# SDDD-PulseBoard-1_0.net
KiCad netlist of a schematic drawn in EAGLE
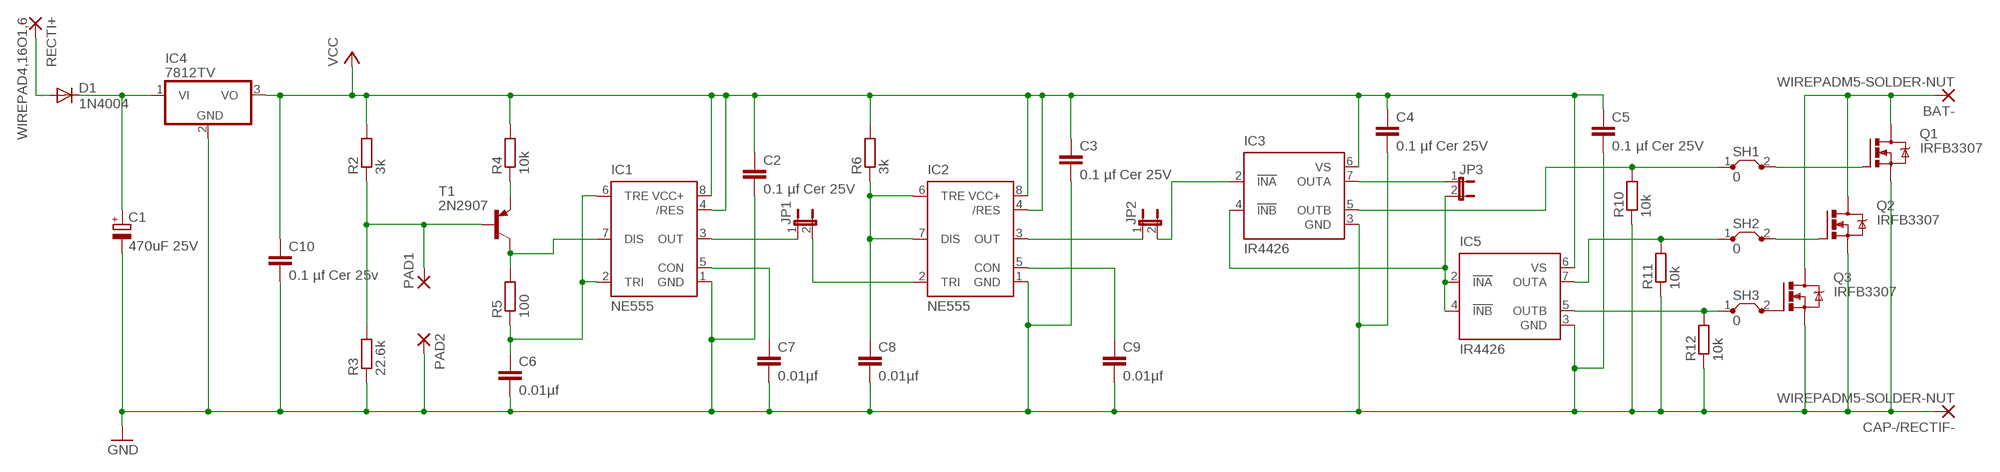
[diagram p0: schematic, sheet 1]

(export (version "E")
  (design (tool "Eeschema 10.0.6"))
  (components
    (comp (ref "BAT-")
      (value "WIREPADM5-SOLDER-NUT")
      (footprint "eagle-import:M5-SOLDER-NUT")
      (libsource (lib "eagle-import") (part "WIREPADM5-SOLDER-NUT"))
    )
    (comp (ref "C1")
      (value "470uF 25V")
      (footprint "eagle-import:E5-8,5")
      (libsource (lib "eagle-import") (part "CPOL-EUE5-8.5"))
    )
    (comp (ref "C2")
      (value "0.1 µf Cer 25V")
      (footprint "eagle-import:C050-025X075")
      (libsource (lib "eagle-import") (part "C-EU050-025X075"))
    )
    (comp (ref "C3")
      (value "0.1 µf Cer 25V")
      (footprint "eagle-import:C050-025X075")
      (libsource (lib "eagle-import") (part "C-EU050-025X075"))
    )
    (comp (ref "C4")
      (value "0.1 µf Cer 25V")
      (footprint "eagle-import:C050-025X075")
      (libsource (lib "eagle-import") (part "C-EU050-025X075"))
    )
    (comp (ref "C5")
      (value "0.1 µf Cer 25V")
      (footprint "eagle-import:C050-025X075")
      (libsource (lib "eagle-import") (part "C-EU050-025X075"))
    )
    (comp (ref "C6")
      (value "0.01µf")
      (footprint "eagle-import:C050-025X075")
      (libsource (lib "eagle-import") (part "C-EU050-025X075"))
    )
    (comp (ref "C7")
      (value "0.01µf")
      (footprint "eagle-import:C050-025X075")
      (libsource (lib "eagle-import") (part "C-EU050-025X075"))
    )
    (comp (ref "C8")
      (value "0.01µf")
      (footprint "eagle-import:C050-025X075")
      (libsource (lib "eagle-import") (part "C-EU050-025X075"))
    )
    (comp (ref "C9")
      (value "0.01µf")
      (footprint "eagle-import:C050-025X075")
      (libsource (lib "eagle-import") (part "C-EU050-025X075"))
    )
    (comp (ref "C10")
      (value "0.1 µf Cer 25v")
      (footprint "eagle-import:C050-025X075")
      (libsource (lib "eagle-import") (part "C-EU050-025X075"))
    )
    (comp (ref "CAP-/RECTIF-")
      (value "WIREPADM5-SOLDER-NUT")
      (footprint "eagle-import:M5-SOLDER-NUT")
      (libsource (lib "eagle-import") (part "WIREPADM5-SOLDER-NUT"))
    )
    (comp (ref "D1")
      (value "1N4004")
      (footprint "eagle-import:DO41-10")
      (libsource (lib "eagle-import") (part "1N4004"))
    )
    (comp (ref "IC1")
      (value "NE555")
      (footprint "eagle-import:DIL-08")
      (fields (field (name "MF") "Arrow Electronics") (field (name "MPN") "NE555N"))
      (libsource (lib "eagle-import") (part "NE555"))
    )
    (comp (ref "IC2")
      (value "NE555")
      (footprint "eagle-import:DIL-08")
      (fields (field (name "MF") "Arrow Electronics") (field (name "MPN") "NE555N"))
      (libsource (lib "eagle-import") (part "NE555"))
    )
    (comp (ref "IC3")
      (value "IR4426")
      (footprint "eagle-import:DIL08")
      (fields (field (name "MF") "INTERNATIONAL RECTIFIER(IR)") (field (name "MPN") "IR4426PBF"))
      (libsource (lib "eagle-import") (part "IR4426"))
    )
    (comp (ref "IC4")
      (value "7812TV")
      (footprint "eagle-import:TO220V")
      (libsource (lib "eagle-import") (part "78TV12"))
    )
    (comp (ref "IC5")
      (value "IR4426")
      (footprint "eagle-import:DIL08")
      (fields (field (name "MF") "INTERNATIONAL RECTIFIER(IR)") (field (name "MPN") "IR4426PBF"))
      (libsource (lib "eagle-import") (part "IR4426"))
    )
    (comp (ref "JP1")
      (value "JP1E")
      (footprint "eagle-import:JP1")
      (libsource (lib "eagle-import") (part "JP1E"))
    )
    (comp (ref "JP2")
      (value "JP1E")
      (footprint "eagle-import:JP1")
      (libsource (lib "eagle-import") (part "JP1E"))
    )
    (comp (ref "JP3")
      (value "JP1E")
      (footprint "eagle-import:JP1")
      (libsource (lib "eagle-import") (part "JP1E"))
    )
    (comp (ref "PAD1")
      (value "2,15/1,0")
      (footprint "eagle-import:2,15_1,0")
      (libsource (lib "eagle-import") (part "2,15/1,0"))
    )
    (comp (ref "PAD2")
      (value "2,15/1,0")
      (footprint "eagle-import:2,15_1,0")
      (libsource (lib "eagle-import") (part "2,15/1,0"))
    )
    (comp (ref "Q1")
      (value "IRFB3307")
      (footprint "eagle-import:TO220BV")
      (libsource (lib "eagle-import") (part "IRF540"))
    )
    (comp (ref "Q2")
      (value "IRFB3307")
      (footprint "eagle-import:TO220BV")
      (libsource (lib "eagle-import") (part "IRF540"))
    )
    (comp (ref "Q3")
      (value "IRFB3307")
      (footprint "eagle-import:TO220BV")
      (libsource (lib "eagle-import") (part "IRF540"))
    )
    (comp (ref "R2")
      (value "3k")
      (footprint "eagle-import:0207_10")
      (libsource (lib "eagle-import") (part "R-EU_0207/10"))
    )
    (comp (ref "R3")
      (value "22.6k")
      (footprint "eagle-import:0207_10")
      (libsource (lib "eagle-import") (part "R-EU_0207/10"))
    )
    (comp (ref "R4")
      (value "10k")
      (footprint "eagle-import:0207_10")
      (libsource (lib "eagle-import") (part "R-EU_0207/10"))
    )
    (comp (ref "R5")
      (value "100")
      (footprint "eagle-import:0207_10")
      (libsource (lib "eagle-import") (part "R-EU_0207/10"))
    )
    (comp (ref "R6")
      (value "3k")
      (footprint "eagle-import:0207_10")
      (libsource (lib "eagle-import") (part "R-EU_0207/10"))
    )
    (comp (ref "R10")
      (value "10k")
      (footprint "eagle-import:0207_10")
      (libsource (lib "eagle-import") (part "R-EU_0207/10"))
    )
    (comp (ref "R11")
      (value "10k")
      (footprint "eagle-import:0207_10")
      (libsource (lib "eagle-import") (part "R-EU_0207/10"))
    )
    (comp (ref "R12")
      (value "10k")
      (footprint "eagle-import:0207_10")
      (libsource (lib "eagle-import") (part "R-EU_0207/10"))
    )
    (comp (ref "RECTI+")
      (value "WIREPAD4,16O1,6")
      (footprint "eagle-import:4,16O1,6")
      (libsource (lib "eagle-import") (part "WIREPAD4,16O1,6"))
    )
    (comp (ref "SH1")
      (value "0")
      (footprint "eagle-import:30")
      (libsource (lib "eagle-import") (part "J30MM"))
    )
    (comp (ref "SH2")
      (value "0")
      (footprint "eagle-import:30")
      (libsource (lib "eagle-import") (part "J30MM"))
    )
    (comp (ref "SH3")
      (value "0")
      (footprint "eagle-import:30")
      (libsource (lib "eagle-import") (part "J30MM"))
    )
    (comp (ref "T1")
      (value "2N2907")
      (footprint "eagle-import:TO92-CBE")
      (libsource (lib "eagle-import") (part "-PNP-TO92-CBEMPS2907A"))
    )
  )
  (nets
    (net (code "1") (name "GND") (class "Default")
      (node (ref "C1") (pin "-") (pinfunction "-_-") (pintype "passive"))
      (node (ref "C10") (pin "2") (pinfunction "2_2") (pintype "passive"))
      (node (ref "C2") (pin "2") (pinfunction "2_2") (pintype "passive"))
      (node (ref "C3") (pin "2") (pinfunction "2_2") (pintype "passive"))
      (node (ref "C4") (pin "2") (pinfunction "2_2") (pintype "passive"))
      (node (ref "C5") (pin "2") (pinfunction "2_2") (pintype "passive"))
      (node (ref "C6") (pin "2") (pinfunction "2_2") (pintype "passive"))
      (node (ref "C7") (pin "2") (pinfunction "2_2") (pintype "passive"))
      (node (ref "C8") (pin "2") (pinfunction "2_2") (pintype "passive"))
      (node (ref "C9") (pin "2") (pinfunction "2_2") (pintype "passive"))
      (node (ref "CAP-/RECTIF-") (pin "1") (pinfunction "P_1") (pintype "passive"))
      (node (ref "CAP-/RECTIF-") (pin "P$1") (pinfunction "P_P$1") (pintype "passive"))
      (node (ref "CAP-/RECTIF-") (pin "P$10") (pinfunction "P_P$10") (pintype "passive"))
      (node (ref "CAP-/RECTIF-") (pin "P$11") (pinfunction "P_P$11") (pintype "passive"))
      (node (ref "CAP-/RECTIF-") (pin "P$12") (pinfunction "P_P$12") (pintype "passive"))
      (node (ref "CAP-/RECTIF-") (pin "P$13") (pinfunction "P_P$13") (pintype "passive"))
      (node (ref "CAP-/RECTIF-") (pin "P$14") (pinfunction "P_P$14") (pintype "passive"))
      (node (ref "CAP-/RECTIF-") (pin "P$15") (pinfunction "P_P$15") (pintype "passive"))
      (node (ref "CAP-/RECTIF-") (pin "P$16") (pinfunction "P_P$16") (pintype "passive"))
      (node (ref "CAP-/RECTIF-") (pin "P$17") (pinfunction "P_P$17") (pintype "passive"))
      (node (ref "CAP-/RECTIF-") (pin "P$18") (pinfunction "P_P$18") (pintype "passive"))
      (node (ref "CAP-/RECTIF-") (pin "P$19") (pinfunction "P_P$19") (pintype "passive"))
      (node (ref "CAP-/RECTIF-") (pin "P$2") (pinfunction "P_P$2") (pintype "passive"))
      (node (ref "CAP-/RECTIF-") (pin "P$20") (pinfunction "P_P$20") (pintype "passive"))
      (node (ref "CAP-/RECTIF-") (pin "P$21") (pinfunction "P_P$21") (pintype "passive"))
      (node (ref "CAP-/RECTIF-") (pin "P$22") (pinfunction "P_P$22") (pintype "passive"))
      (node (ref "CAP-/RECTIF-") (pin "P$23") (pinfunction "P_P$23") (pintype "passive"))
      (node (ref "CAP-/RECTIF-") (pin "P$24") (pinfunction "P_P$24") (pintype "passive"))
      (node (ref "CAP-/RECTIF-") (pin "P$25") (pinfunction "P_P$25") (pintype "passive"))
      (node (ref "CAP-/RECTIF-") (pin "P$26") (pinfunction "P_P$26") (pintype "passive"))
      (node (ref "CAP-/RECTIF-") (pin "P$27") (pinfunction "P_P$27") (pintype "passive"))
      (node (ref "CAP-/RECTIF-") (pin "P$28") (pinfunction "P_P$28") (pintype "passive"))
      (node (ref "CAP-/RECTIF-") (pin "P$29") (pinfunction "P_P$29") (pintype "passive"))
      (node (ref "CAP-/RECTIF-") (pin "P$3") (pinfunction "P_P$3") (pintype "passive"))
      (node (ref "CAP-/RECTIF-") (pin "P$30") (pinfunction "P_P$30") (pintype "passive"))
      (node (ref "CAP-/RECTIF-") (pin "P$31") (pinfunction "P_P$31") (pintype "passive"))
      (node (ref "CAP-/RECTIF-") (pin "P$32") (pinfunction "P_P$32") (pintype "passive"))
      (node (ref "CAP-/RECTIF-") (pin "P$33") (pinfunction "P_P$33") (pintype "passive"))
      (node (ref "CAP-/RECTIF-") (pin "P$34") (pinfunction "P_P$34") (pintype "passive"))
      (node (ref "CAP-/RECTIF-") (pin "P$35") (pinfunction "P_P$35") (pintype "passive"))
      (node (ref "CAP-/RECTIF-") (pin "P$36") (pinfunction "P_P$36") (pintype "passive"))
      (node (ref "CAP-/RECTIF-") (pin "P$37") (pinfunction "P_P$37") (pintype "passive"))
      (node (ref "CAP-/RECTIF-") (pin "P$38") (pinfunction "P_P$38") (pintype "passive"))
      (node (ref "CAP-/RECTIF-") (pin "P$39") (pinfunction "P_P$39") (pintype "passive"))
      (node (ref "CAP-/RECTIF-") (pin "P$4") (pinfunction "P_P$4") (pintype "passive"))
      (node (ref "CAP-/RECTIF-") (pin "P$40") (pinfunction "P_P$40") (pintype "passive"))
      (node (ref "CAP-/RECTIF-") (pin "P$41") (pinfunction "P_P$41") (pintype "passive"))
      (node (ref "CAP-/RECTIF-") (pin "P$42") (pinfunction "P_P$42") (pintype "passive"))
      (node (ref "CAP-/RECTIF-") (pin "P$43") (pinfunction "P_P$43") (pintype "passive"))
      (node (ref "CAP-/RECTIF-") (pin "P$44") (pinfunction "P_P$44") (pintype "passive"))
      (node (ref "CAP-/RECTIF-") (pin "P$45") (pinfunction "P_P$45") (pintype "passive"))
      (node (ref "CAP-/RECTIF-") (pin "P$46") (pinfunction "P_P$46") (pintype "passive"))
      (node (ref "CAP-/RECTIF-") (pin "P$47") (pinfunction "P_P$47") (pintype "passive"))
      (node (ref "CAP-/RECTIF-") (pin "P$48") (pinfunction "P_P$48") (pintype "passive"))
      (node (ref "CAP-/RECTIF-") (pin "P$49") (pinfunction "P_P$49") (pintype "passive"))
      (node (ref "CAP-/RECTIF-") (pin "P$5") (pinfunction "P_P$5") (pintype "passive"))
      (node (ref "CAP-/RECTIF-") (pin "P$50") (pinfunction "P_P$50") (pintype "passive"))
      (node (ref "CAP-/RECTIF-") (pin "P$51") (pinfunction "P_P$51") (pintype "passive"))
      (node (ref "CAP-/RECTIF-") (pin "P$52") (pinfunction "P_P$52") (pintype "passive"))
      (node (ref "CAP-/RECTIF-") (pin "P$53") (pinfunction "P_P$53") (pintype "passive"))
      (node (ref "CAP-/RECTIF-") (pin "P$54") (pinfunction "P_P$54") (pintype "passive"))
      (node (ref "CAP-/RECTIF-") (pin "P$55") (pinfunction "P_P$55") (pintype "passive"))
      (node (ref "CAP-/RECTIF-") (pin "P$56") (pinfunction "P_P$56") (pintype "passive"))
      (node (ref "CAP-/RECTIF-") (pin "P$57") (pinfunction "P_P$57") (pintype "passive"))
      (node (ref "CAP-/RECTIF-") (pin "P$58") (pinfunction "P_P$58") (pintype "passive"))
      (node (ref "CAP-/RECTIF-") (pin "P$59") (pinfunction "P_P$59") (pintype "passive"))
      (node (ref "CAP-/RECTIF-") (pin "P$6") (pinfunction "P_P$6") (pintype "passive"))
      (node (ref "CAP-/RECTIF-") (pin "P$60") (pinfunction "P_P$60") (pintype "passive"))
      (node (ref "CAP-/RECTIF-") (pin "P$61") (pinfunction "P_P$61") (pintype "passive"))
      (node (ref "CAP-/RECTIF-") (pin "P$62") (pinfunction "P_P$62") (pintype "passive"))
      (node (ref "CAP-/RECTIF-") (pin "P$63") (pinfunction "P_P$63") (pintype "passive"))
      (node (ref "CAP-/RECTIF-") (pin "P$64") (pinfunction "P_P$64") (pintype "passive"))
      (node (ref "CAP-/RECTIF-") (pin "P$65") (pinfunction "P_P$65") (pintype "passive"))
      (node (ref "CAP-/RECTIF-") (pin "P$66") (pinfunction "P_P$66") (pintype "passive"))
      (node (ref "CAP-/RECTIF-") (pin "P$67") (pinfunction "P_P$67") (pintype "passive"))
      (node (ref "CAP-/RECTIF-") (pin "P$68") (pinfunction "P_P$68") (pintype "passive"))
      (node (ref "CAP-/RECTIF-") (pin "P$69") (pinfunction "P_P$69") (pintype "passive"))
      (node (ref "CAP-/RECTIF-") (pin "P$7") (pinfunction "P_P$7") (pintype "passive"))
      (node (ref "CAP-/RECTIF-") (pin "P$70") (pinfunction "P_P$70") (pintype "passive"))
      (node (ref "CAP-/RECTIF-") (pin "P$71") (pinfunction "P_P$71") (pintype "passive"))
      (node (ref "CAP-/RECTIF-") (pin "P$72") (pinfunction "P_P$72") (pintype "passive"))
      (node (ref "CAP-/RECTIF-") (pin "P$73") (pinfunction "P_P$73") (pintype "passive"))
      (node (ref "CAP-/RECTIF-") (pin "P$74") (pinfunction "P_P$74") (pintype "passive"))
      (node (ref "CAP-/RECTIF-") (pin "P$75") (pinfunction "P_P$75") (pintype "passive"))
      (node (ref "CAP-/RECTIF-") (pin "P$76") (pinfunction "P_P$76") (pintype "passive"))
      (node (ref "CAP-/RECTIF-") (pin "P$77") (pinfunction "P_P$77") (pintype "passive"))
      (node (ref "CAP-/RECTIF-") (pin "P$78") (pinfunction "P_P$78") (pintype "passive"))
      (node (ref "CAP-/RECTIF-") (pin "P$79") (pinfunction "P_P$79") (pintype "passive"))
      (node (ref "CAP-/RECTIF-") (pin "P$8") (pinfunction "P_P$8") (pintype "passive"))
      (node (ref "CAP-/RECTIF-") (pin "P$80") (pinfunction "P_P$80") (pintype "passive"))
      (node (ref "CAP-/RECTIF-") (pin "P$9") (pinfunction "P_P$9") (pintype "passive"))
      (node (ref "IC1") (pin "1") (pinfunction "GND_1") (pintype "power_in"))
      (node (ref "IC2") (pin "1") (pinfunction "GND_1") (pintype "power_in"))
      (node (ref "IC3") (pin "3") (pinfunction "GND_3") (pintype "power_in"))
      (node (ref "IC4") (pin "2") (pinfunction "GND_2") (pintype "passive"))
      (node (ref "IC5") (pin "3") (pinfunction "GND_3") (pintype "power_in"))
      (node (ref "PAD2") (pin "1") (pinfunction "P_1") (pintype "passive"))
      (node (ref "Q1") (pin "S") (pinfunction "S_S") (pintype "passive"))
      (node (ref "Q2") (pin "S") (pinfunction "S_S") (pintype "passive"))
      (node (ref "Q3") (pin "S") (pinfunction "S_S") (pintype "passive"))
      (node (ref "R10") (pin "1") (pinfunction "1_1") (pintype "passive"))
      (node (ref "R11") (pin "1") (pinfunction "1_1") (pintype "passive"))
      (node (ref "R12") (pin "1") (pinfunction "1_1") (pintype "passive"))
      (node (ref "R3") (pin "1") (pinfunction "1_1") (pintype "passive"))
    )
    (net (code "2") (name "Net-(BAT--P-Pad1)") (class "Default")
      (node (ref "BAT-") (pin "1") (pinfunction "P_1") (pintype "passive"))
      (node (ref "BAT-") (pin "P$1") (pinfunction "P_P$1") (pintype "passive"))
      (node (ref "BAT-") (pin "P$10") (pinfunction "P_P$10") (pintype "passive"))
      (node (ref "BAT-") (pin "P$11") (pinfunction "P_P$11") (pintype "passive"))
      (node (ref "BAT-") (pin "P$12") (pinfunction "P_P$12") (pintype "passive"))
      (node (ref "BAT-") (pin "P$13") (pinfunction "P_P$13") (pintype "passive"))
      (node (ref "BAT-") (pin "P$14") (pinfunction "P_P$14") (pintype "passive"))
      (node (ref "BAT-") (pin "P$15") (pinfunction "P_P$15") (pintype "passive"))
      (node (ref "BAT-") (pin "P$16") (pinfunction "P_P$16") (pintype "passive"))
      (node (ref "BAT-") (pin "P$17") (pinfunction "P_P$17") (pintype "passive"))
      (node (ref "BAT-") (pin "P$18") (pinfunction "P_P$18") (pintype "passive"))
      (node (ref "BAT-") (pin "P$19") (pinfunction "P_P$19") (pintype "passive"))
      (node (ref "BAT-") (pin "P$2") (pinfunction "P_P$2") (pintype "passive"))
      (node (ref "BAT-") (pin "P$20") (pinfunction "P_P$20") (pintype "passive"))
      (node (ref "BAT-") (pin "P$21") (pinfunction "P_P$21") (pintype "passive"))
      (node (ref "BAT-") (pin "P$22") (pinfunction "P_P$22") (pintype "passive"))
      (node (ref "BAT-") (pin "P$23") (pinfunction "P_P$23") (pintype "passive"))
      (node (ref "BAT-") (pin "P$24") (pinfunction "P_P$24") (pintype "passive"))
      (node (ref "BAT-") (pin "P$25") (pinfunction "P_P$25") (pintype "passive"))
      (node (ref "BAT-") (pin "P$26") (pinfunction "P_P$26") (pintype "passive"))
      (node (ref "BAT-") (pin "P$27") (pinfunction "P_P$27") (pintype "passive"))
      (node (ref "BAT-") (pin "P$28") (pinfunction "P_P$28") (pintype "passive"))
      (node (ref "BAT-") (pin "P$29") (pinfunction "P_P$29") (pintype "passive"))
      (node (ref "BAT-") (pin "P$3") (pinfunction "P_P$3") (pintype "passive"))
      (node (ref "BAT-") (pin "P$30") (pinfunction "P_P$30") (pintype "passive"))
      (node (ref "BAT-") (pin "P$31") (pinfunction "P_P$31") (pintype "passive"))
      (node (ref "BAT-") (pin "P$32") (pinfunction "P_P$32") (pintype "passive"))
      (node (ref "BAT-") (pin "P$33") (pinfunction "P_P$33") (pintype "passive"))
      (node (ref "BAT-") (pin "P$34") (pinfunction "P_P$34") (pintype "passive"))
      (node (ref "BAT-") (pin "P$35") (pinfunction "P_P$35") (pintype "passive"))
      (node (ref "BAT-") (pin "P$36") (pinfunction "P_P$36") (pintype "passive"))
      (node (ref "BAT-") (pin "P$37") (pinfunction "P_P$37") (pintype "passive"))
      (node (ref "BAT-") (pin "P$38") (pinfunction "P_P$38") (pintype "passive"))
      (node (ref "BAT-") (pin "P$39") (pinfunction "P_P$39") (pintype "passive"))
      (node (ref "BAT-") (pin "P$4") (pinfunction "P_P$4") (pintype "passive"))
      (node (ref "BAT-") (pin "P$40") (pinfunction "P_P$40") (pintype "passive"))
      (node (ref "BAT-") (pin "P$41") (pinfunction "P_P$41") (pintype "passive"))
      (node (ref "BAT-") (pin "P$42") (pinfunction "P_P$42") (pintype "passive"))
      (node (ref "BAT-") (pin "P$43") (pinfunction "P_P$43") (pintype "passive"))
      (node (ref "BAT-") (pin "P$44") (pinfunction "P_P$44") (pintype "passive"))
      (node (ref "BAT-") (pin "P$45") (pinfunction "P_P$45") (pintype "passive"))
      (node (ref "BAT-") (pin "P$46") (pinfunction "P_P$46") (pintype "passive"))
      (node (ref "BAT-") (pin "P$47") (pinfunction "P_P$47") (pintype "passive"))
      (node (ref "BAT-") (pin "P$48") (pinfunction "P_P$48") (pintype "passive"))
      (node (ref "BAT-") (pin "P$49") (pinfunction "P_P$49") (pintype "passive"))
      (node (ref "BAT-") (pin "P$5") (pinfunction "P_P$5") (pintype "passive"))
      (node (ref "BAT-") (pin "P$50") (pinfunction "P_P$50") (pintype "passive"))
      (node (ref "BAT-") (pin "P$51") (pinfunction "P_P$51") (pintype "passive"))
      (node (ref "BAT-") (pin "P$52") (pinfunction "P_P$52") (pintype "passive"))
      (node (ref "BAT-") (pin "P$53") (pinfunction "P_P$53") (pintype "passive"))
      (node (ref "BAT-") (pin "P$54") (pinfunction "P_P$54") (pintype "passive"))
      (node (ref "BAT-") (pin "P$55") (pinfunction "P_P$55") (pintype "passive"))
      (node (ref "BAT-") (pin "P$56") (pinfunction "P_P$56") (pintype "passive"))
      (node (ref "BAT-") (pin "P$57") (pinfunction "P_P$57") (pintype "passive"))
      (node (ref "BAT-") (pin "P$58") (pinfunction "P_P$58") (pintype "passive"))
      (node (ref "BAT-") (pin "P$59") (pinfunction "P_P$59") (pintype "passive"))
      (node (ref "BAT-") (pin "P$6") (pinfunction "P_P$6") (pintype "passive"))
      (node (ref "BAT-") (pin "P$60") (pinfunction "P_P$60") (pintype "passive"))
      (node (ref "BAT-") (pin "P$61") (pinfunction "P_P$61") (pintype "passive"))
      (node (ref "BAT-") (pin "P$62") (pinfunction "P_P$62") (pintype "passive"))
      (node (ref "BAT-") (pin "P$63") (pinfunction "P_P$63") (pintype "passive"))
      (node (ref "BAT-") (pin "P$64") (pinfunction "P_P$64") (pintype "passive"))
      (node (ref "BAT-") (pin "P$65") (pinfunction "P_P$65") (pintype "passive"))
      (node (ref "BAT-") (pin "P$66") (pinfunction "P_P$66") (pintype "passive"))
      (node (ref "BAT-") (pin "P$67") (pinfunction "P_P$67") (pintype "passive"))
      (node (ref "BAT-") (pin "P$68") (pinfunction "P_P$68") (pintype "passive"))
      (node (ref "BAT-") (pin "P$69") (pinfunction "P_P$69") (pintype "passive"))
      (node (ref "BAT-") (pin "P$7") (pinfunction "P_P$7") (pintype "passive"))
      (node (ref "BAT-") (pin "P$70") (pinfunction "P_P$70") (pintype "passive"))
      (node (ref "BAT-") (pin "P$71") (pinfunction "P_P$71") (pintype "passive"))
      (node (ref "BAT-") (pin "P$72") (pinfunction "P_P$72") (pintype "passive"))
      (node (ref "BAT-") (pin "P$73") (pinfunction "P_P$73") (pintype "passive"))
      (node (ref "BAT-") (pin "P$74") (pinfunction "P_P$74") (pintype "passive"))
      (node (ref "BAT-") (pin "P$75") (pinfunction "P_P$75") (pintype "passive"))
      (node (ref "BAT-") (pin "P$76") (pinfunction "P_P$76") (pintype "passive"))
      (node (ref "BAT-") (pin "P$77") (pinfunction "P_P$77") (pintype "passive"))
      (node (ref "BAT-") (pin "P$78") (pinfunction "P_P$78") (pintype "passive"))
      (node (ref "BAT-") (pin "P$79") (pinfunction "P_P$79") (pintype "passive"))
      (node (ref "BAT-") (pin "P$8") (pinfunction "P_P$8") (pintype "passive"))
      (node (ref "BAT-") (pin "P$80") (pinfunction "P_P$80") (pintype "passive"))
      (node (ref "BAT-") (pin "P$9") (pinfunction "P_P$9") (pintype "passive"))
      (node (ref "Q1") (pin "D") (pinfunction "D_D") (pintype "passive"))
      (node (ref "Q2") (pin "D") (pinfunction "D_D") (pintype "passive"))
      (node (ref "Q3") (pin "D") (pinfunction "D_D") (pintype "passive"))
    )
    (net (code "3") (name "Net-(IC1-CON)") (class "Default")
      (node (ref "C7") (pin "1") (pinfunction "1_1") (pintype "passive"))
      (node (ref "IC1") (pin "5") (pinfunction "CON_5") (pintype "input"))
    )
    (net (code "4") (name "Net-(IC1-DIS)") (class "Default")
      (node (ref "IC1") (pin "7") (pinfunction "DIS_7") (pintype "input"))
      (node (ref "R5") (pin "2") (pinfunction "2_2") (pintype "passive"))
      (node (ref "T1") (pin "C") (pinfunction "C_C") (pintype "passive"))
    )
    (net (code "5") (name "Net-(IC1-OUT)") (class "Default")
      (node (ref "IC1") (pin "3") (pinfunction "OUT_3") (pintype "output"))
      (node (ref "JP1") (pin "1") (pinfunction "1_1") (pintype "passive"))
    )
    (net (code "6") (name "Net-(IC1-TRE)") (class "Default")
      (node (ref "C6") (pin "1") (pinfunction "1_1") (pintype "passive"))
      (node (ref "IC1") (pin "2") (pinfunction "TRI_2") (pintype "input"))
      (node (ref "IC1") (pin "6") (pinfunction "TRE_6") (pintype "input"))
      (node (ref "R5") (pin "1") (pinfunction "1_1") (pintype "passive"))
    )
    (net (code "7") (name "Net-(IC2-CON)") (class "Default")
      (node (ref "C9") (pin "1") (pinfunction "1_1") (pintype "passive"))
      (node (ref "IC2") (pin "5") (pinfunction "CON_5") (pintype "input"))
    )
    (net (code "8") (name "Net-(IC2-DIS)") (class "Default")
      (node (ref "C8") (pin "1") (pinfunction "1_1") (pintype "passive"))
      (node (ref "IC2") (pin "6") (pinfunction "TRE_6") (pintype "input"))
      (node (ref "IC2") (pin "7") (pinfunction "DIS_7") (pintype "input"))
      (node (ref "R6") (pin "1") (pinfunction "1_1") (pintype "passive"))
    )
    (net (code "9") (name "Net-(IC2-OUT)") (class "Default")
      (node (ref "IC2") (pin "3") (pinfunction "OUT_3") (pintype "output"))
      (node (ref "JP2") (pin "1") (pinfunction "1_1") (pintype "passive"))
    )
    (net (code "10") (name "Net-(IC2-TRI)") (class "Default")
      (node (ref "IC2") (pin "2") (pinfunction "TRI_2") (pintype "input"))
      (node (ref "JP1") (pin "2") (pinfunction "2_2") (pintype "passive"))
    )
    (net (code "11") (name "Net-(IC3-OUTA)") (class "Default")
      (node (ref "IC3") (pin "7") (pinfunction "OUTA_7") (pintype "output"))
      (node (ref "JP3") (pin "1") (pinfunction "1_1") (pintype "passive"))
    )
    (net (code "12") (name "Net-(IC3-OUTB)") (class "Default")
      (node (ref "IC3") (pin "5") (pinfunction "OUTB_5") (pintype "output"))
      (node (ref "R10") (pin "2") (pinfunction "2_2") (pintype "passive"))
      (node (ref "SH1") (pin "1") (pinfunction "1_1") (pintype "passive"))
    )
    (net (code "13") (name "Net-(IC3-~{INA})") (class "Default")
      (node (ref "IC3") (pin "2") (pinfunction "~{INA}_2") (pintype "input"))
      (node (ref "JP2") (pin "2") (pinfunction "2_2") (pintype "passive"))
    )
    (net (code "14") (name "Net-(IC3-~{INB})") (class "Default")
      (node (ref "IC3") (pin "4") (pinfunction "~{INB}_4") (pintype "input"))
      (node (ref "IC5") (pin "2") (pinfunction "~{INA}_2") (pintype "input"))
      (node (ref "IC5") (pin "4") (pinfunction "~{INB}_4") (pintype "input"))
      (node (ref "JP3") (pin "2") (pinfunction "2_2") (pintype "passive"))
    )
    (net (code "15") (name "Net-(IC4-VI)") (class "Default")
      (node (ref "C1") (pin "+") (pinfunction "+_+") (pintype "passive"))
      (node (ref "D1") (pin "C") (pinfunction "C_C") (pintype "passive"))
      (node (ref "IC4") (pin "1") (pinfunction "VI_1") (pintype "input"))
    )
    (net (code "16") (name "Net-(IC5-OUTA)") (class "Default")
      (node (ref "IC5") (pin "7") (pinfunction "OUTA_7") (pintype "output"))
      (node (ref "R11") (pin "2") (pinfunction "2_2") (pintype "passive"))
      (node (ref "SH2") (pin "1") (pinfunction "1_1") (pintype "passive"))
    )
    (net (code "17") (name "Net-(IC5-OUTB)") (class "Default")
      (node (ref "IC5") (pin "5") (pinfunction "OUTB_5") (pintype "output"))
      (node (ref "R12") (pin "2") (pinfunction "2_2") (pintype "passive"))
      (node (ref "SH3") (pin "1") (pinfunction "1_1") (pintype "passive"))
    )
    (net (code "18") (name "Net-(PAD1-P)") (class "Default")
      (node (ref "PAD1") (pin "1") (pinfunction "P_1") (pintype "passive"))
      (node (ref "R2") (pin "1") (pinfunction "1_1") (pintype "passive"))
      (node (ref "R3") (pin "2") (pinfunction "2_2") (pintype "passive"))
      (node (ref "T1") (pin "B") (pinfunction "B_B") (pintype "passive"))
    )
    (net (code "19") (name "Net-(Q1-PadG)") (class "Default")
      (node (ref "Q1") (pin "G") (pinfunction "G_G") (pintype "passive"))
      (node (ref "SH1") (pin "2") (pinfunction "2_2") (pintype "passive"))
    )
    (net (code "20") (name "Net-(Q2-PadG)") (class "Default")
      (node (ref "Q2") (pin "G") (pinfunction "G_G") (pintype "passive"))
      (node (ref "SH2") (pin "2") (pinfunction "2_2") (pintype "passive"))
    )
    (net (code "21") (name "Net-(Q3-PadG)") (class "Default")
      (node (ref "Q3") (pin "G") (pinfunction "G_G") (pintype "passive"))
      (node (ref "SH3") (pin "2") (pinfunction "2_2") (pintype "passive"))
    )
    (net (code "22") (name "Net-(R4-Pad1)") (class "Default")
      (node (ref "R4") (pin "1") (pinfunction "1_1") (pintype "passive"))
      (node (ref "T1") (pin "E") (pinfunction "E_E") (pintype "passive"))
    )
    (net (code "23") (name "Net-(RECTI+-P)") (class "Default")
      (node (ref "D1") (pin "A") (pinfunction "A_A") (pintype "passive"))
      (node (ref "RECTI+") (pin "1") (pinfunction "P_1") (pintype "passive"))
    )
    (net (code "24") (name "VCC") (class "Default")
      (node (ref "C10") (pin "1") (pinfunction "1_1") (pintype "passive"))
      (node (ref "C2") (pin "1") (pinfunction "1_1") (pintype "passive"))
      (node (ref "C3") (pin "1") (pinfunction "1_1") (pintype "passive"))
      (node (ref "C4") (pin "1") (pinfunction "1_1") (pintype "passive"))
      (node (ref "C5") (pin "1") (pinfunction "1_1") (pintype "passive"))
      (node (ref "IC1") (pin "4") (pinfunction "/RES_4") (pintype "input"))
      (node (ref "IC1") (pin "8") (pinfunction "VCC+_8") (pintype "power_in"))
      (node (ref "IC2") (pin "4") (pinfunction "/RES_4") (pintype "input"))
      (node (ref "IC2") (pin "8") (pinfunction "VCC+_8") (pintype "power_in"))
      (node (ref "IC3") (pin "6") (pinfunction "VS_6") (pintype "power_in"))
      (node (ref "IC4") (pin "3") (pinfunction "VO_3") (pintype "passive"))
      (node (ref "IC5") (pin "6") (pinfunction "VS_6") (pintype "power_in"))
      (node (ref "R2") (pin "2") (pinfunction "2_2") (pintype "passive"))
      (node (ref "R4") (pin "2") (pinfunction "2_2") (pintype "passive"))
      (node (ref "R6") (pin "2") (pinfunction "2_2") (pintype "passive"))
    )
  )
)
